# sound-op-switch.net
KiCad netlist of a schematic drawn in EAGLE
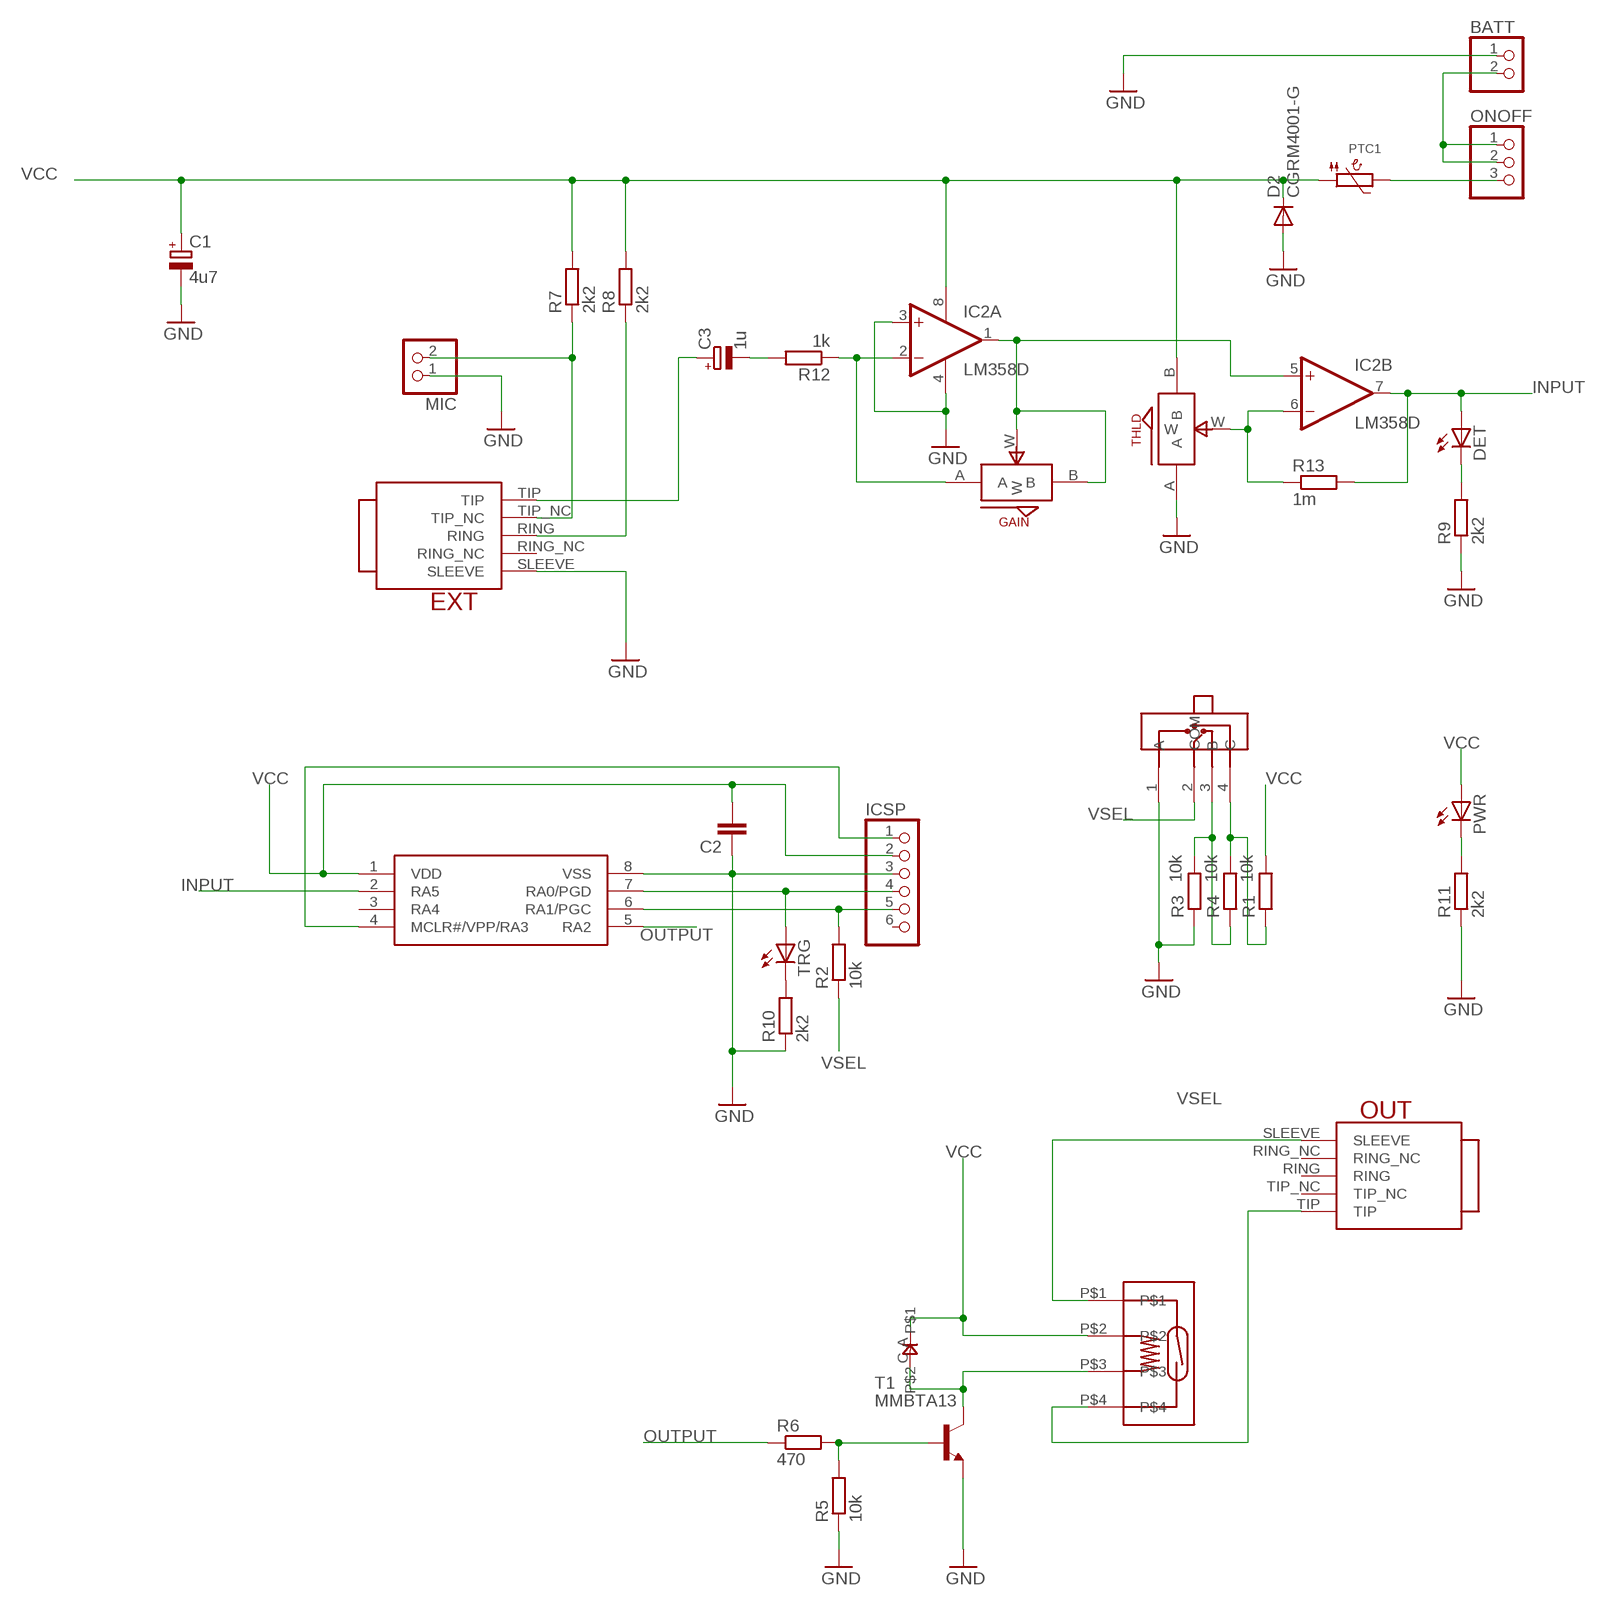
[diagram p0: schematic, sheet 1]

(export (version "E")
  (design (tool "Eeschema 10.0.6"))
  (components
    (comp (ref "BATT")
      (value "PINHD-1X2")
      (footprint "eagle-import:1X02")
      (libsource (lib "eagle-import") (part "PINHD-1X2"))
    )
    (comp (ref "C1")
      (value "4u7")
      (footprint "eagle-import:E2,5-6E")
      (libsource (lib "eagle-import") (part "CPOL-EUE2,5-6E"))
    )
    (comp (ref "C2")
      (value "C-EUC0805")
      (footprint "eagle-import:C0805")
      (libsource (lib "eagle-import") (part "C-EUC0805"))
    )
    (comp (ref "C3")
      (value "1u")
      (footprint "eagle-import:E2,5-6E")
      (libsource (lib "eagle-import") (part "CPOL-EUE2,5-6E"))
    )
    (comp (ref "D1")
      (value "0805DIODE")
      (footprint "eagle-import:0805DIODE")
      (libsource (lib "eagle-import") (part "0805DIODE"))
    )
    (comp (ref "D2")
      (value "CGRM4001-G")
      (footprint "eagle-import:SOD-123_MINI-SMA")
      (libsource (lib "eagle-import") (part "CGRM400-G1"))
    )
    (comp (ref "DET")
      (value "LED3MM")
      (footprint "eagle-import:LED3MM")
      (libsource (lib "eagle-import") (part "LED3MM"))
    )
    (comp (ref "EXT")
      (value "TRUCONNECTJACK")
      (footprint "eagle-import:TRUCONNECTJACK")
      (libsource (lib "eagle-import") (part "TRUCONNECTJACK"))
    )
    (comp (ref "GAIN")
      (value "ALPS_POT_SMALL")
      (footprint "eagle-import:SMALL_ALPS_POT")
      (libsource (lib "eagle-import") (part "ALPS_POT_SMALL"))
    )
    (comp (ref "IC1")
      (value "PIC12F1822")
      (footprint "eagle-import:DIL08")
      (libsource (lib "eagle-import") (part "PIC12F1822"))
    )
    (comp (ref "IC2")
      (value "LM358D")
      (footprint "eagle-import:SO08")
      (libsource (lib "eagle-import") (part "LM358D"))
    )
    (comp (ref "ICSP")
      (value "PINHD-1X6")
      (footprint "eagle-import:1X06")
      (libsource (lib "eagle-import") (part "PINHD-1X6"))
    )
    (comp (ref "MIC")
      (value "PINHD-1X2")
      (footprint "eagle-import:1X02")
      (libsource (lib "eagle-import") (part "PINHD-1X2"))
    )
    (comp (ref "MODE")
      (value "SP4T-SLIDE")
      (footprint "eagle-import:SP3T-SLIDE")
      (libsource (lib "eagle-import") (part "SP4T-SLIDE"))
    )
    (comp (ref "ONOFF")
      (value "PINHD-1X3")
      (footprint "eagle-import:1X03")
      (libsource (lib "eagle-import") (part "PINHD-1X3"))
    )
    (comp (ref "OUT")
      (value "TRUCONNECTJACK")
      (footprint "eagle-import:TRUCONNECTJACK")
      (libsource (lib "eagle-import") (part "TRUCONNECTJACK"))
    )
    (comp (ref "PTC1")
      (value "PTC1206")
      (footprint "eagle-import:1206")
      (libsource (lib "eagle-import") (part "PTC1206"))
    )
    (comp (ref "PWR")
      (value "LED3MM")
      (footprint "eagle-import:LED3MM")
      (libsource (lib "eagle-import") (part "LED3MM"))
    )
    (comp (ref "R1")
      (value "10k")
      (footprint "eagle-import:R0805")
      (libsource (lib "eagle-import") (part "resistor_R-EU_R0805"))
    )
    (comp (ref "R2")
      (value "10k")
      (footprint "eagle-import:R0805")
      (libsource (lib "eagle-import") (part "resistor_R-EU_R0805"))
    )
    (comp (ref "R3")
      (value "10k")
      (footprint "eagle-import:R0805")
      (libsource (lib "eagle-import") (part "resistor_R-EU_R0805"))
    )
    (comp (ref "R4")
      (value "10k")
      (footprint "eagle-import:R0805")
      (libsource (lib "eagle-import") (part "resistor_R-EU_R0805"))
    )
    (comp (ref "R5")
      (value "10k")
      (footprint "eagle-import:R0805")
      (libsource (lib "eagle-import") (part "resistor_R-EU_R0805"))
    )
    (comp (ref "R6")
      (value "470")
      (footprint "eagle-import:R0805")
      (libsource (lib "eagle-import") (part "resistor_R-EU_R0805"))
    )
    (comp (ref "R7")
      (value "2k2")
      (footprint "eagle-import:R0805")
      (libsource (lib "eagle-import") (part "resistor_R-EU_R0805"))
    )
    (comp (ref "R8")
      (value "2k2")
      (footprint "eagle-import:R0805")
      (libsource (lib "eagle-import") (part "resistor_R-EU_R0805"))
    )
    (comp (ref "R9")
      (value "2k2")
      (footprint "eagle-import:R0805")
      (libsource (lib "eagle-import") (part "resistor_R-EU_R0805"))
    )
    (comp (ref "R10")
      (value "2k2")
      (footprint "eagle-import:R0805")
      (libsource (lib "eagle-import") (part "resistor_R-EU_R0805"))
    )
    (comp (ref "R11")
      (value "2k2")
      (footprint "eagle-import:R0805")
      (libsource (lib "eagle-import") (part "resistor_R-EU_R0805"))
    )
    (comp (ref "R12")
      (value "1k")
      (footprint "eagle-import:R0805")
      (libsource (lib "eagle-import") (part "R-EU_R0805"))
    )
    (comp (ref "R13")
      (value "1m")
      (footprint "eagle-import:R0805")
      (libsource (lib "eagle-import") (part "resistor_R-EU_R0805"))
    )
    (comp (ref "RLY1")
      (value "9007-REED-RELAY")
      (footprint "eagle-import:9007-REED-RELAY")
      (libsource (lib "eagle-import") (part "9007-REED-RELAY"))
    )
    (comp (ref "T1")
      (value "MMBTA13")
      (footprint "eagle-import:SOT23-BEC")
      (libsource (lib "eagle-import") (part "-NPN-SOT23-BECMMBT3904LT1"))
    )
    (comp (ref "THLD")
      (value "ALPS_POT_SMALL")
      (footprint "eagle-import:SMALL_ALPS_POT")
      (libsource (lib "eagle-import") (part "ALPS_POT_SMALL"))
    )
    (comp (ref "TRG")
      (value "LED3MM")
      (footprint "eagle-import:LED3MM")
      (libsource (lib "eagle-import") (part "LED3MM"))
    )
  )
  (nets
    (net (code "1") (name "/INPUT") (class "Default")
      (node (ref "DET") (pin "A") (pinfunction "A_A") (pintype "passive"))
      (node (ref "IC1") (pin "2") (pinfunction "RA5_2") (pintype "bidirectional"))
      (node (ref "IC2") (pin "7") (pinfunction "OUT_7") (pintype "output"))
      (node (ref "R13") (pin "2") (pinfunction "2_2") (pintype "passive"))
    )
    (net (code "2") (name "/OUTPUT") (class "Default")
      (node (ref "IC1") (pin "5") (pinfunction "RA2_5") (pintype "bidirectional"))
      (node (ref "R6") (pin "1") (pinfunction "1_1") (pintype "passive"))
    )
    (net (code "3") (name "/VCC") (class "Default")
      (node (ref "C1") (pin "+") (pinfunction "+_+") (pintype "passive"))
      (node (ref "C2") (pin "2") (pinfunction "2_2") (pintype "passive"))
      (node (ref "D1") (pin "A") (pinfunction "P$2_A") (pintype "bidirectional"))
      (node (ref "D2") (pin "C") (pinfunction "C_C") (pintype "passive"))
      (node (ref "IC1") (pin "1") (pinfunction "VDD_1") (pintype "power_in"))
      (node (ref "IC2") (pin "8") (pinfunction "V+_8") (pintype "power_in"))
      (node (ref "ICSP") (pin "2") (pinfunction "2_2") (pintype "passive"))
      (node (ref "PTC1") (pin "1") (pinfunction "1_1") (pintype "passive"))
      (node (ref "PWR") (pin "A") (pinfunction "A_A") (pintype "passive"))
      (node (ref "R1") (pin "2") (pinfunction "2_2") (pintype "passive"))
      (node (ref "R7") (pin "2") (pinfunction "2_2") (pintype "passive"))
      (node (ref "R8") (pin "2") (pinfunction "2_2") (pintype "passive"))
      (node (ref "RLY1") (pin "P$2") (pinfunction "P$2_P$2") (pintype "bidirectional"))
      (node (ref "THLD") (pin "B") (pinfunction "B_B") (pintype "bidirectional"))
    )
    (net (code "4") (name "/VSEL") (class "Default")
      (node (ref "MODE") (pin "2") (pinfunction "COM_2") (pintype "bidirectional"))
      (node (ref "R2") (pin "1") (pinfunction "1_1") (pintype "passive"))
    )
    (net (code "5") (name "GND") (class "Default")
      (node (ref "BATT") (pin "1") (pinfunction "1_1") (pintype "passive"))
      (node (ref "C1") (pin "-") (pinfunction "-_-") (pintype "passive"))
      (node (ref "C2") (pin "1") (pinfunction "1_1") (pintype "passive"))
      (node (ref "D2") (pin "A") (pinfunction "A_A") (pintype "passive"))
      (node (ref "EXT") (pin "SLEEVE") (pinfunction "SLEEVE_SLEEVE") (pintype "bidirectional"))
      (node (ref "IC1") (pin "8") (pinfunction "VSS_8") (pintype "power_in"))
      (node (ref "IC2") (pin "3") (pinfunction "+IN_3") (pintype "input"))
      (node (ref "IC2") (pin "4") (pinfunction "V-_4") (pintype "power_in"))
      (node (ref "ICSP") (pin "3") (pinfunction "3_3") (pintype "passive"))
      (node (ref "MIC") (pin "1") (pinfunction "1_1") (pintype "passive"))
      (node (ref "MODE") (pin "1") (pinfunction "A_1") (pintype "bidirectional"))
      (node (ref "R10") (pin "1") (pinfunction "1_1") (pintype "passive"))
      (node (ref "R11") (pin "1") (pinfunction "1_1") (pintype "passive"))
      (node (ref "R3") (pin "1") (pinfunction "1_1") (pintype "passive"))
      (node (ref "R5") (pin "1") (pinfunction "1_1") (pintype "passive"))
      (node (ref "R9") (pin "1") (pinfunction "1_1") (pintype "passive"))
      (node (ref "T1") (pin "E") (pinfunction "E_E") (pintype "passive"))
      (node (ref "THLD") (pin "A") (pinfunction "A_A") (pintype "bidirectional"))
    )
    (net (code "6") (name "Net-(BATT-Pad2)") (class "Default")
      (node (ref "BATT") (pin "2") (pinfunction "2_2") (pintype "passive"))
      (node (ref "ONOFF") (pin "1") (pinfunction "1_1") (pintype "passive"))
      (node (ref "ONOFF") (pin "2") (pinfunction "2_2") (pintype "passive"))
    )
    (net (code "7") (name "Net-(C3-Pad+)") (class "Default")
      (node (ref "C3") (pin "+") (pinfunction "+_+") (pintype "passive"))
      (node (ref "EXT") (pin "TIP") (pinfunction "TIP_TIP") (pintype "bidirectional"))
    )
    (net (code "8") (name "Net-(C3-Pad-)") (class "Default")
      (node (ref "C3") (pin "-") (pinfunction "-_-") (pintype "passive"))
      (node (ref "R12") (pin "2") (pinfunction "2_2") (pintype "passive"))
    )
    (net (code "9") (name "Net-(D1-P$1)") (class "Default")
      (node (ref "D1") (pin "C") (pinfunction "P$1_C") (pintype "bidirectional"))
      (node (ref "RLY1") (pin "P$3") (pinfunction "P$3_P$3") (pintype "bidirectional"))
      (node (ref "T1") (pin "C") (pinfunction "C_C") (pintype "passive"))
    )
    (net (code "10") (name "Net-(DET-C)") (class "Default")
      (node (ref "DET") (pin "K") (pinfunction "C_K") (pintype "passive"))
      (node (ref "R9") (pin "2") (pinfunction "2_2") (pintype "passive"))
    )
    (net (code "11") (name "Net-(EXT-PadRING)") (class "Default")
      (node (ref "EXT") (pin "RING") (pinfunction "RING_RING") (pintype "bidirectional"))
      (node (ref "R8") (pin "1") (pinfunction "1_1") (pintype "passive"))
    )
    (net (code "12") (name "Net-(EXT-PadTIP_NC)") (class "Default")
      (node (ref "EXT") (pin "TIP_NC") (pinfunction "TIP_NC_TIP_NC") (pintype "bidirectional"))
      (node (ref "MIC") (pin "2") (pinfunction "2_2") (pintype "passive"))
      (node (ref "R7") (pin "1") (pinfunction "1_1") (pintype "passive"))
    )
    (net (code "13") (name "Net-(IC1-MCLR#{slash}VPP{slash}RA3)") (class "Default")
      (node (ref "IC1") (pin "4") (pinfunction "MCLR#/VPP/RA3_4") (pintype "bidirectional"))
      (node (ref "ICSP") (pin "1") (pinfunction "1_1") (pintype "passive"))
    )
    (net (code "14") (name "Net-(IC1-RA0{slash}PGD)") (class "Default")
      (node (ref "IC1") (pin "7") (pinfunction "RA0/PGD_7") (pintype "bidirectional"))
      (node (ref "ICSP") (pin "4") (pinfunction "4_4") (pintype "passive"))
      (node (ref "TRG") (pin "A") (pinfunction "A_A") (pintype "passive"))
    )
    (net (code "15") (name "Net-(IC1-RA1{slash}PGC)") (class "Default")
      (node (ref "IC1") (pin "6") (pinfunction "RA1/PGC_6") (pintype "bidirectional"))
      (node (ref "ICSP") (pin "5") (pinfunction "5_5") (pintype "passive"))
      (node (ref "R2") (pin "2") (pinfunction "2_2") (pintype "passive"))
    )
    (net (code "16") (name "Net-(IC2A--IN)") (class "Default")
      (node (ref "GAIN") (pin "A") (pinfunction "A_A") (pintype "bidirectional"))
      (node (ref "IC2") (pin "2") (pinfunction "-IN_2") (pintype "input"))
      (node (ref "R12") (pin "1") (pinfunction "1_1") (pintype "passive"))
    )
    (net (code "17") (name "Net-(IC2A-OUT)") (class "Default")
      (node (ref "GAIN") (pin "B") (pinfunction "B_B") (pintype "bidirectional"))
      (node (ref "GAIN") (pin "W") (pinfunction "W_W") (pintype "bidirectional"))
      (node (ref "IC2") (pin "1") (pinfunction "OUT_1") (pintype "output"))
      (node (ref "IC2") (pin "5") (pinfunction "+IN_5") (pintype "input"))
    )
    (net (code "18") (name "Net-(IC2B--IN)") (class "Default")
      (node (ref "IC2") (pin "6") (pinfunction "-IN_6") (pintype "input"))
      (node (ref "R13") (pin "1") (pinfunction "1_1") (pintype "passive"))
      (node (ref "THLD") (pin "W") (pinfunction "W_W") (pintype "bidirectional"))
    )
    (net (code "19") (name "Net-(MODE-B)") (class "Default")
      (node (ref "MODE") (pin "3") (pinfunction "B_3") (pintype "bidirectional"))
      (node (ref "R3") (pin "2") (pinfunction "2_2") (pintype "passive"))
      (node (ref "R4") (pin "1") (pinfunction "1_1") (pintype "passive"))
    )
    (net (code "20") (name "Net-(MODE-C)") (class "Default")
      (node (ref "MODE") (pin "4") (pinfunction "C_4") (pintype "bidirectional"))
      (node (ref "R1") (pin "1") (pinfunction "1_1") (pintype "passive"))
      (node (ref "R4") (pin "2") (pinfunction "2_2") (pintype "passive"))
    )
    (net (code "21") (name "Net-(ONOFF-Pad3)") (class "Default")
      (node (ref "ONOFF") (pin "3") (pinfunction "3_3") (pintype "passive"))
      (node (ref "PTC1") (pin "2") (pinfunction "2_2") (pintype "passive"))
    )
    (net (code "22") (name "Net-(OUT-PadSLEEVE)") (class "Default")
      (node (ref "OUT") (pin "SLEEVE") (pinfunction "SLEEVE_SLEEVE") (pintype "bidirectional"))
      (node (ref "RLY1") (pin "P$1") (pinfunction "P$1_P$1") (pintype "bidirectional"))
    )
    (net (code "23") (name "Net-(OUT-PadTIP)") (class "Default")
      (node (ref "OUT") (pin "TIP") (pinfunction "TIP_TIP") (pintype "bidirectional"))
      (node (ref "RLY1") (pin "P$4") (pinfunction "P$4_P$4") (pintype "bidirectional"))
    )
    (net (code "24") (name "Net-(PWR-C)") (class "Default")
      (node (ref "PWR") (pin "K") (pinfunction "C_K") (pintype "passive"))
      (node (ref "R11") (pin "2") (pinfunction "2_2") (pintype "passive"))
    )
    (net (code "25") (name "Net-(R5-Pad2)") (class "Default")
      (node (ref "R5") (pin "2") (pinfunction "2_2") (pintype "passive"))
      (node (ref "R6") (pin "2") (pinfunction "2_2") (pintype "passive"))
      (node (ref "T1") (pin "B") (pinfunction "B_B") (pintype "passive"))
    )
    (net (code "26") (name "Net-(TRG-C)") (class "Default")
      (node (ref "R10") (pin "2") (pinfunction "2_2") (pintype "passive"))
      (node (ref "TRG") (pin "K") (pinfunction "C_K") (pintype "passive"))
    )
    (net (code "27") (name "unconnected-(EXT-PadRING_NC)") (class "Default")
      (node (ref "EXT") (pin "RING_NC") (pinfunction "RING_NC_RING_NC") (pintype "bidirectional"))
    )
    (net (code "28") (name "unconnected-(IC1-RA4-Pad3)") (class "Default")
      (node (ref "IC1") (pin "3") (pinfunction "RA4_3") (pintype "bidirectional"))
    )
    (net (code "29") (name "unconnected-(ICSP-Pad6)") (class "Default")
      (node (ref "ICSP") (pin "6") (pinfunction "6_6") (pintype "passive"))
    )
    (net (code "30") (name "unconnected-(OUT-PadRING)") (class "Default")
      (node (ref "OUT") (pin "RING") (pinfunction "RING_RING") (pintype "bidirectional"))
    )
    (net (code "31") (name "unconnected-(OUT-PadRING_NC)") (class "Default")
      (node (ref "OUT") (pin "RING_NC") (pinfunction "RING_NC_RING_NC") (pintype "bidirectional"))
    )
    (net (code "32") (name "unconnected-(OUT-PadTIP_NC)") (class "Default")
      (node (ref "OUT") (pin "TIP_NC") (pinfunction "TIP_NC_TIP_NC") (pintype "bidirectional"))
    )
  )
)
